# PWC.net
KiCad netlist of a schematic drawn in EAGLE
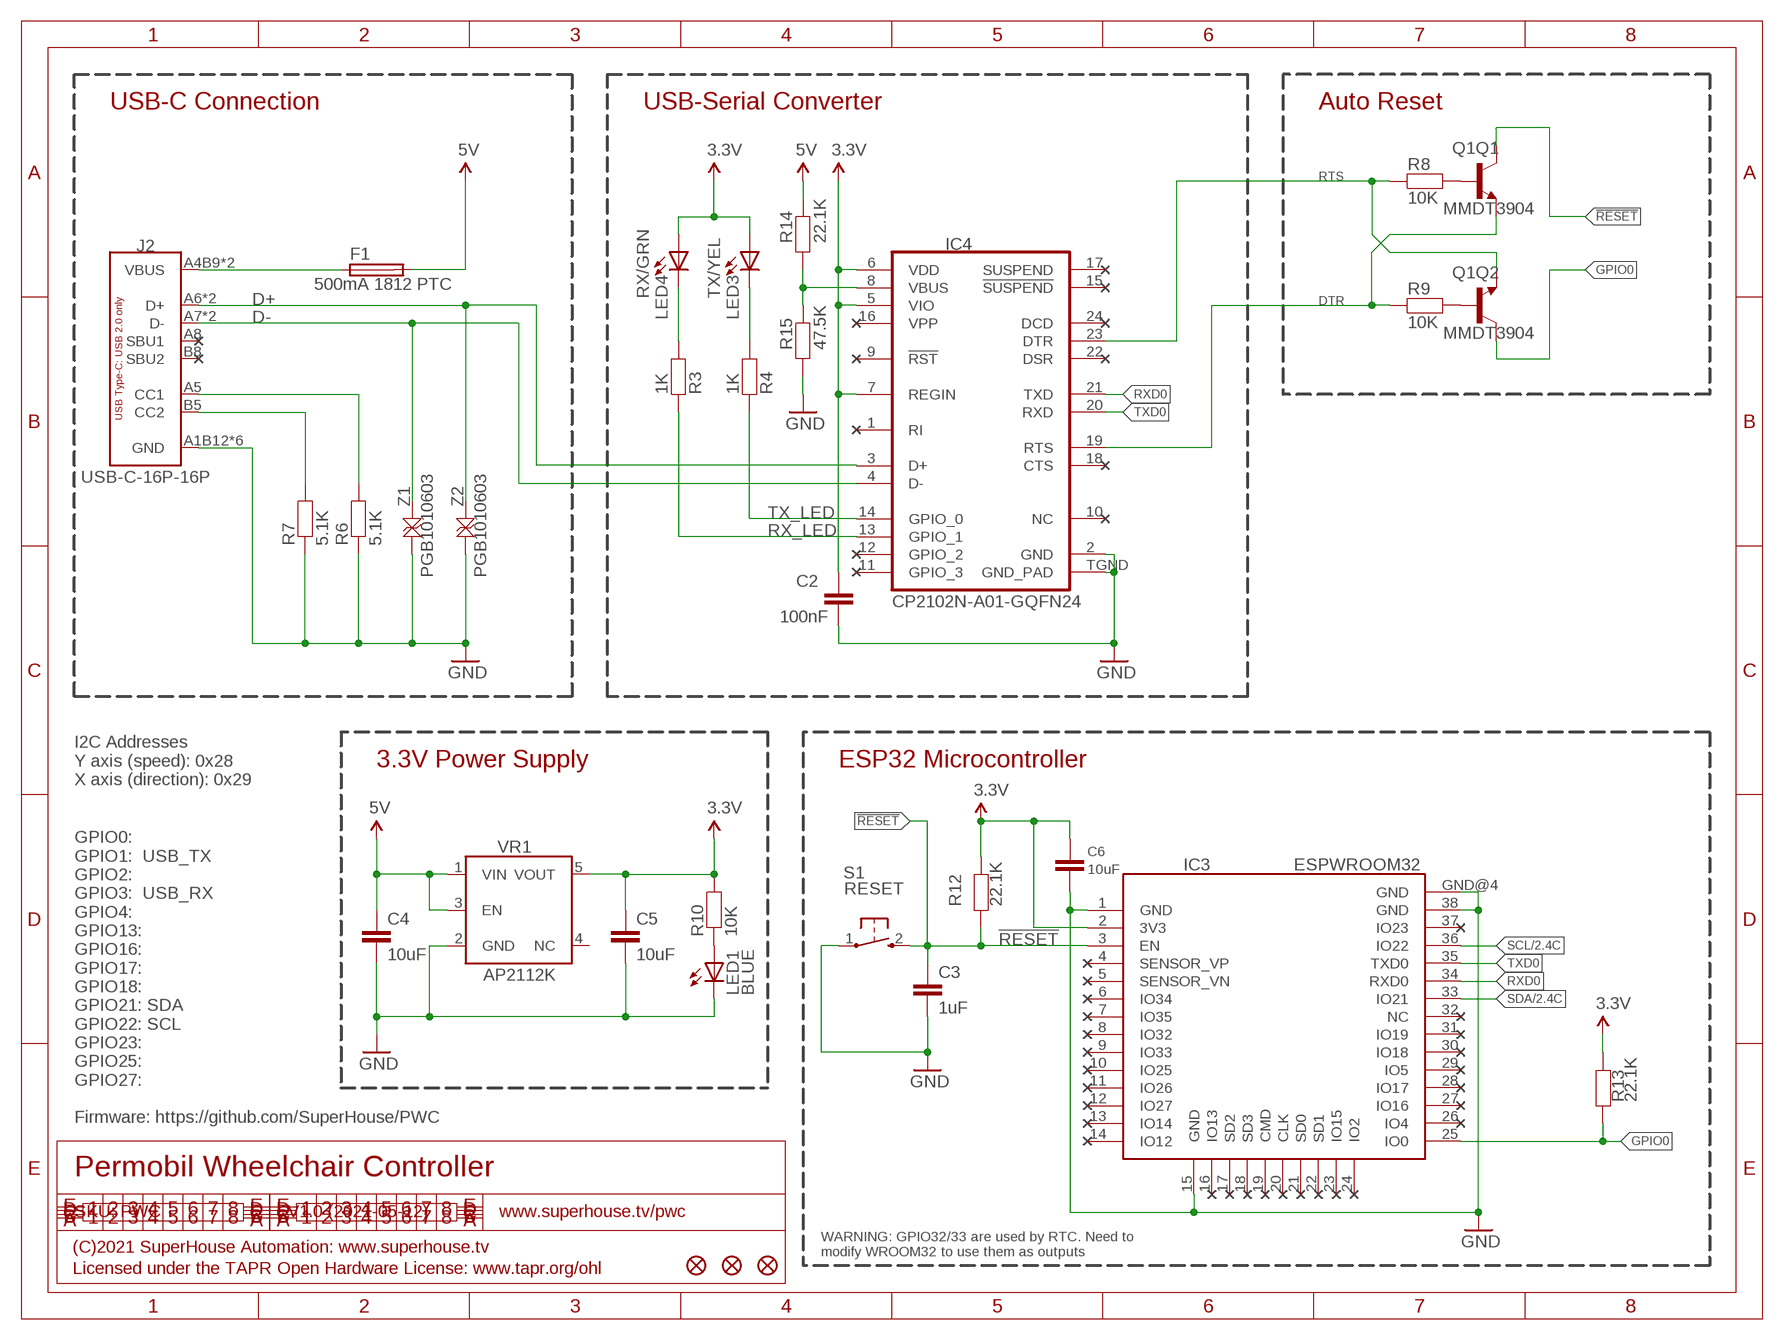
[diagram p0: schematic, sheet 1]
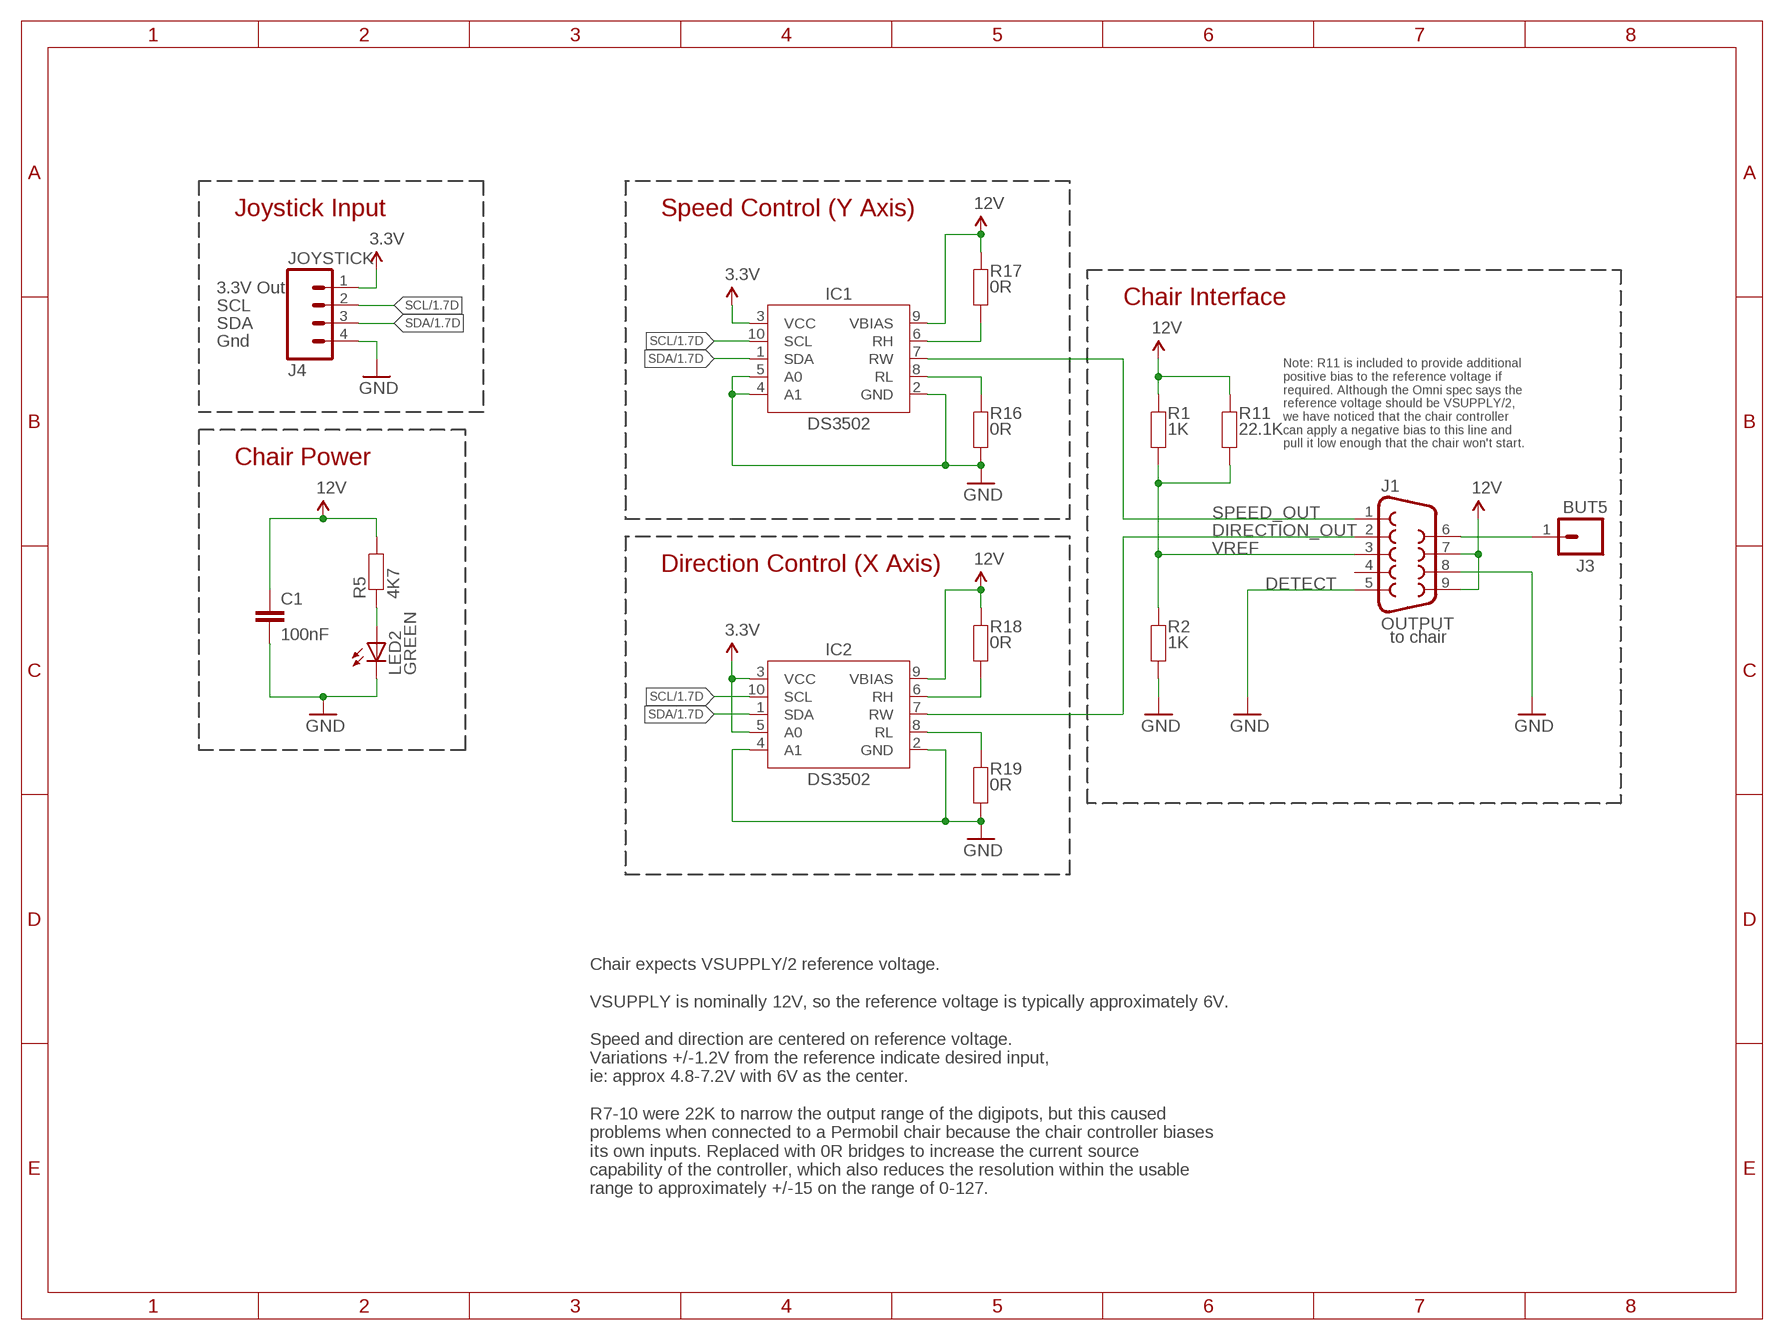
[diagram p1: schematic, sheet 2]

(export (version "E")
  (design (tool "Eeschema 10.0.6"))
  (components
    (comp (ref "C2")
      (value "100nF")
      (footprint "eagle-import:C0603")
      (libsource (lib "eagle-import") (part "CAP0603"))
    )
    (comp (ref "C3")
      (value "1uF")
      (footprint "eagle-import:C0603")
      (libsource (lib "eagle-import") (part "CAP0603"))
    )
    (comp (ref "C4")
      (value "10uF")
      (footprint "eagle-import:C0805")
      (libsource (lib "eagle-import") (part "CAP0805"))
    )
    (comp (ref "C5")
      (value "10uF")
      (footprint "eagle-import:C0805")
      (libsource (lib "eagle-import") (part "CAP0805"))
    )
    (comp (ref "C6")
      (value "10uF")
      (footprint "eagle-import:C0805")
      (libsource (lib "eagle-import") (part "CAP0805"))
    )
    (comp (ref "F1")
      (value "500mA 1812 PTC")
      (footprint "eagle-import:1812")
      (libsource (lib "eagle-import") (part "PTC-1812050"))
    )
    (comp (ref "IC3")
      (value "ESPWROOM32")
      (footprint "eagle-import:ESPWROOM32")
      (libsource (lib "eagle-import") (part "ESPWROOM32"))
    )
    (comp (ref "IC4")
      (value "CP2102N-A01-GQFN24")
      (footprint "eagle-import:QFN-24")
      (libsource (lib "eagle-import") (part "CP2104"))
    )
    (comp (ref "J2")
      (value "USB-C-16P-16P")
      (footprint "eagle-import:USB-C-16P")
      (libsource (lib "eagle-import") (part "USB-C-16P-16P"))
    )
    (comp (ref "LED1")
      (value "BLUE")
      (footprint "eagle-import:LED-0603")
      (libsource (lib "eagle-import") (part "LED0603"))
    )
    (comp (ref "LED3")
      (value "TX/YEL")
      (footprint "eagle-import:LED-0603")
      (libsource (lib "eagle-import") (part "LED0603"))
    )
    (comp (ref "LED4")
      (value "RX/GRN")
      (footprint "eagle-import:LED-0603")
      (libsource (lib "eagle-import") (part "LED0603"))
    )
    (comp (ref "Q1")
      (value "MMDT3904")
      (footprint "eagle-import:SOT-363")
      (libsource (lib "eagle-import") (part "TRANS_NPN_DUAL-MMDT3904"))
    )
    (comp (ref "R3")
      (value "1K")
      (footprint "eagle-import:R0603")
      (libsource (lib "eagle-import") (part "RESISTOR0603"))
    )
    (comp (ref "R4")
      (value "1K")
      (footprint "eagle-import:R0603")
      (libsource (lib "eagle-import") (part "RESISTOR0603"))
    )
    (comp (ref "R6")
      (value "5.1K")
      (footprint "eagle-import:R0603")
      (libsource (lib "eagle-import") (part "RESISTOR0603"))
    )
    (comp (ref "R7")
      (value "5.1K")
      (footprint "eagle-import:R0603")
      (libsource (lib "eagle-import") (part "RESISTOR0603"))
    )
    (comp (ref "R8")
      (value "10K")
      (footprint "eagle-import:R0603")
      (libsource (lib "eagle-import") (part "RESISTOR0603"))
    )
    (comp (ref "R9")
      (value "10K")
      (footprint "eagle-import:R0603")
      (libsource (lib "eagle-import") (part "RESISTOR0603"))
    )
    (comp (ref "R10")
      (value "10K")
      (footprint "eagle-import:R0603")
      (libsource (lib "eagle-import") (part "RESISTOR0603"))
    )
    (comp (ref "R12")
      (value "22.1K")
      (footprint "eagle-import:R0603")
      (libsource (lib "eagle-import") (part "RESISTOR0603"))
    )
    (comp (ref "R13")
      (value "22.1K")
      (footprint "eagle-import:R0603")
      (libsource (lib "eagle-import") (part "RESISTOR0603"))
    )
    (comp (ref "R14")
      (value "22.1K")
      (footprint "eagle-import:R0603")
      (libsource (lib "eagle-import") (part "RESISTOR0603"))
    )
    (comp (ref "R15")
      (value "47.5K")
      (footprint "eagle-import:R0603")
      (libsource (lib "eagle-import") (part "RESISTOR0603"))
    )
    (comp (ref "S1")
      (value "RESET")
      (footprint "eagle-import:TACTILE_SMT_3X4X2")
      (libsource (lib "eagle-import") (part "TAC_SWITCH_2PINSMT"))
    )
    (comp (ref "U$35")
      (value "FIDUCIAL1X2")
      (footprint "eagle-import:FIDUCIAL-1X2")
      (libsource (lib "eagle-import") (part "FIDUCIAL1X2"))
    )
    (comp (ref "U$36")
      (value "FIDUCIAL1X2")
      (footprint "eagle-import:FIDUCIAL-1X2")
      (libsource (lib "eagle-import") (part "FIDUCIAL1X2"))
    )
    (comp (ref "U$37")
      (value "FIDUCIAL1X2")
      (footprint "eagle-import:FIDUCIAL-1X2")
      (libsource (lib "eagle-import") (part "FIDUCIAL1X2"))
    )
    (comp (ref "VR1")
      (value "AP2112KSOT25")
      (footprint "eagle-import:SOT23-5")
      (libsource (lib "eagle-import") (part "AP2112KSOT25"))
    )
    (comp (ref "Z1")
      (value "PGB1010603")
      (footprint "eagle-import:TVS0603")
      (libsource (lib "eagle-import") (part "TVS0603"))
    )
    (comp (ref "Z2")
      (value "PGB1010603")
      (footprint "eagle-import:TVS0603")
      (libsource (lib "eagle-import") (part "TVS0603"))
    )
    (comp (ref "C1")
      (value "100nF")
      (footprint "eagle-import:C0603")
      (libsource (lib "eagle-import") (part "CAP0603"))
    )
    (comp (ref "IC1")
      (value "DS3502")
      (footprint "eagle-import:MSOP10")
      (libsource (lib "eagle-import") (part "DS3502"))
    )
    (comp (ref "IC2")
      (value "DS3502")
      (footprint "eagle-import:MSOP10")
      (libsource (lib "eagle-import") (part "DS3502"))
    )
    (comp (ref "J1")
      (value "OUTPUT")
      (footprint "eagle-import:DB9-PCB-SOCKET")
      (libsource (lib "eagle-import") (part "DB9-PCB-SOCKET"))
    )
    (comp (ref "J3")
      (value "BUT5")
      (footprint "eagle-import:1X01")
      (libsource (lib "eagle-import") (part "M01-PLAIN"))
    )
    (comp (ref "J4")
      (value "JOYSTICK")
      (footprint "eagle-import:1X04")
      (libsource (lib "eagle-import") (part "M04-PLAIN"))
    )
    (comp (ref "LED2")
      (value "GREEN")
      (footprint "eagle-import:LED-0603")
      (libsource (lib "eagle-import") (part "LED0603"))
    )
    (comp (ref "R1")
      (value "1K")
      (footprint "eagle-import:R0603")
      (libsource (lib "eagle-import") (part "RESISTOR0603"))
    )
    (comp (ref "R2")
      (value "1K")
      (footprint "eagle-import:R0603")
      (libsource (lib "eagle-import") (part "RESISTOR0603"))
    )
    (comp (ref "R5")
      (value "4K7")
      (footprint "eagle-import:R0603")
      (libsource (lib "eagle-import") (part "RESISTOR0603"))
    )
    (comp (ref "R11")
      (value "22.1K")
      (footprint "eagle-import:R0603")
      (libsource (lib "eagle-import") (part "RESISTOR0603"))
    )
    (comp (ref "R16")
      (value "0R")
      (footprint "eagle-import:R0603")
      (libsource (lib "eagle-import") (part "RESISTOR0603"))
    )
    (comp (ref "R17")
      (value "0R")
      (footprint "eagle-import:R0603")
      (libsource (lib "eagle-import") (part "RESISTOR0603"))
    )
    (comp (ref "R18")
      (value "0R")
      (footprint "eagle-import:R0603")
      (libsource (lib "eagle-import") (part "RESISTOR0603"))
    )
    (comp (ref "R19")
      (value "0R")
      (footprint "eagle-import:R0603")
      (libsource (lib "eagle-import") (part "RESISTOR0603"))
    )
  )
  (nets
    (net (code "1") (name "3.3V") (class "Default")
      (node (ref "C2") (pin "1") (pinfunction "1_1") (pintype "passive"))
      (node (ref "C5") (pin "1") (pinfunction "1_1") (pintype "passive"))
      (node (ref "C6") (pin "1") (pinfunction "1_1") (pintype "passive"))
      (node (ref "IC1") (pin "3") (pinfunction "VCC_3") (pintype "power_in"))
      (node (ref "IC2") (pin "3") (pinfunction "VCC_3") (pintype "power_in"))
      (node (ref "IC2") (pin "5") (pinfunction "A0_5") (pintype "input"))
      (node (ref "IC3") (pin "2") (pinfunction "3V3_2") (pintype "power_in"))
      (node (ref "IC4") (pin "5") (pinfunction "VIO_5") (pintype "bidirectional"))
      (node (ref "IC4") (pin "6") (pinfunction "VDD_6") (pintype "power_in"))
      (node (ref "IC4") (pin "7") (pinfunction "REGIN_7") (pintype "power_in"))
      (node (ref "J4") (pin "1") (pinfunction "1_1") (pintype "passive"))
      (node (ref "LED3") (pin "A") (pinfunction "A_A") (pintype "passive"))
      (node (ref "LED4") (pin "A") (pinfunction "A_A") (pintype "passive"))
      (node (ref "R10") (pin "2") (pinfunction "2_2") (pintype "passive"))
      (node (ref "R12") (pin "1") (pinfunction "1_1") (pintype "passive"))
      (node (ref "R13") (pin "1") (pinfunction "1_1") (pintype "passive"))
      (node (ref "VR1") (pin "5") (pinfunction "VOUT_5") (pintype "bidirectional"))
    )
    (net (code "2") (name "5V") (class "Default")
      (node (ref "C4") (pin "1") (pinfunction "1_1") (pintype "passive"))
      (node (ref "F1") (pin "2") (pinfunction "2_2") (pintype "passive"))
      (node (ref "R14") (pin "2") (pinfunction "2_2") (pintype "passive"))
      (node (ref "VR1") (pin "1") (pinfunction "VIN_1") (pintype "bidirectional"))
      (node (ref "VR1") (pin "3") (pinfunction "EN_3") (pintype "bidirectional"))
    )
    (net (code "3") (name "12V") (class "Default")
      (node (ref "C1") (pin "1") (pinfunction "1_1") (pintype "passive"))
      (node (ref "IC1") (pin "9") (pinfunction "VBIAS_9") (pintype "power_in"))
      (node (ref "IC2") (pin "9") (pinfunction "VBIAS_9") (pintype "power_in"))
      (node (ref "J1") (pin "7") (pinfunction "7_7") (pintype "passive"))
      (node (ref "J1") (pin "9") (pinfunction "9_9") (pintype "passive"))
      (node (ref "R1") (pin "2") (pinfunction "2_2") (pintype "passive"))
      (node (ref "R11") (pin "2") (pinfunction "2_2") (pintype "passive"))
      (node (ref "R17") (pin "2") (pinfunction "2_2") (pintype "passive"))
      (node (ref "R18") (pin "2") (pinfunction "2_2") (pintype "passive"))
      (node (ref "R5") (pin "2") (pinfunction "2_2") (pintype "passive"))
    )
    (net (code "4") (name "D+") (class "Default")
      (node (ref "IC4") (pin "3") (pinfunction "D+_3") (pintype "bidirectional"))
      (node (ref "J2") (pin "A6") (pinfunction "D+_A6") (pintype "bidirectional"))
      (node (ref "J2") (pin "B6") (pinfunction "D+_B6") (pintype "bidirectional"))
      (node (ref "Z2") (pin "2") (pinfunction "2_2") (pintype "passive"))
    )
    (net (code "5") (name "D-") (class "Default")
      (node (ref "IC4") (pin "4") (pinfunction "D-_4") (pintype "bidirectional"))
      (node (ref "J2") (pin "A7") (pinfunction "D-_A7") (pintype "bidirectional"))
      (node (ref "J2") (pin "B7") (pinfunction "D-_B7") (pintype "bidirectional"))
      (node (ref "Z1") (pin "2") (pinfunction "2_2") (pintype "passive"))
    )
    (net (code "6") (name "DIRECTION_OUT") (class "Default")
      (node (ref "IC2") (pin "7") (pinfunction "RW_7") (pintype "passive"))
      (node (ref "J1") (pin "2") (pinfunction "2_2") (pintype "passive"))
    )
    (net (code "7") (name "DTR") (class "Default")
      (node (ref "IC4") (pin "23") (pinfunction "DTR_23") (pintype "output"))
      (node (ref "Q1") (pin "1") (pinfunction "E_1") (pintype "passive"))
      (node (ref "R8") (pin "1") (pinfunction "1_1") (pintype "passive"))
    )
    (net (code "8") (name "GND") (class "Default")
      (node (ref "C1") (pin "2") (pinfunction "2_2") (pintype "passive"))
      (node (ref "C2") (pin "2") (pinfunction "2_2") (pintype "passive"))
      (node (ref "C3") (pin "2") (pinfunction "2_2") (pintype "passive"))
      (node (ref "C4") (pin "2") (pinfunction "2_2") (pintype "passive"))
      (node (ref "C5") (pin "2") (pinfunction "2_2") (pintype "passive"))
      (node (ref "C6") (pin "2") (pinfunction "2_2") (pintype "passive"))
      (node (ref "IC1") (pin "2") (pinfunction "GND_2") (pintype "power_in"))
      (node (ref "IC1") (pin "4") (pinfunction "A1_4") (pintype "input"))
      (node (ref "IC1") (pin "5") (pinfunction "A0_5") (pintype "input"))
      (node (ref "IC2") (pin "2") (pinfunction "GND_2") (pintype "power_in"))
      (node (ref "IC2") (pin "4") (pinfunction "A1_4") (pintype "input"))
      (node (ref "IC3") (pin "1") (pinfunction "GND_1") (pintype "power_in"))
      (node (ref "IC3") (pin "15") (pinfunction "GND_15") (pintype "power_in"))
      (node (ref "IC3") (pin "38") (pinfunction "GND_38") (pintype "power_in"))
      (node (ref "IC3") (pin "GND@4") (pinfunction "GND_GND@4") (pintype "power_in"))
      (node (ref "IC4") (pin "2") (pinfunction "GND_2") (pintype "power_in"))
      (node (ref "IC4") (pin "TGND") (pinfunction "GND_PAD_TGND") (pintype "power_in"))
      (node (ref "J1") (pin "5") (pinfunction "5_5") (pintype "passive"))
      (node (ref "J1") (pin "8") (pinfunction "8_8") (pintype "passive"))
      (node (ref "J2") (pin "A12B1") (pinfunction "GND_A12B1") (pintype "power_in"))
      (node (ref "J2") (pin "A1B12") (pinfunction "GND_A1B12") (pintype "power_in"))
      (node (ref "J2") (pin "FIX1") (pinfunction "GND_FIX1") (pintype "power_in"))
      (node (ref "J2") (pin "FIX2") (pinfunction "GND_FIX2") (pintype "power_in"))
      (node (ref "J2") (pin "FIX3") (pinfunction "GND_FIX3") (pintype "power_in"))
      (node (ref "J2") (pin "FIX4") (pinfunction "GND_FIX4") (pintype "power_in"))
      (node (ref "J4") (pin "4") (pinfunction "4_4") (pintype "passive"))
      (node (ref "LED1") (pin "C") (pinfunction "C_C") (pintype "passive"))
      (node (ref "LED2") (pin "C") (pinfunction "C_C") (pintype "passive"))
      (node (ref "R15") (pin "1") (pinfunction "1_1") (pintype "passive"))
      (node (ref "R16") (pin "1") (pinfunction "1_1") (pintype "passive"))
      (node (ref "R19") (pin "1") (pinfunction "1_1") (pintype "passive"))
      (node (ref "R2") (pin "1") (pinfunction "1_1") (pintype "passive"))
      (node (ref "R6") (pin "1") (pinfunction "1_1") (pintype "passive"))
      (node (ref "R7") (pin "1") (pinfunction "1_1") (pintype "passive"))
      (node (ref "S1") (pin "1") (pinfunction "P_1") (pintype "passive"))
      (node (ref "VR1") (pin "2") (pinfunction "GND_2") (pintype "bidirectional"))
      (node (ref "Z1") (pin "1") (pinfunction "1_1") (pintype "passive"))
      (node (ref "Z2") (pin "1") (pinfunction "1_1") (pintype "passive"))
    )
    (net (code "9") (name "GPIO0") (class "Default")
      (node (ref "IC3") (pin "25") (pinfunction "IO0_25") (pintype "bidirectional"))
      (node (ref "Q1") (pin "6") (pinfunction "C_6") (pintype "passive"))
      (node (ref "R13") (pin "2") (pinfunction "2_2") (pintype "passive"))
    )
    (net (code "10") (name "Net-(F1-Pad1)") (class "Default")
      (node (ref "F1") (pin "1") (pinfunction "1_1") (pintype "passive"))
      (node (ref "J2") (pin "A4B9") (pinfunction "VBUS_A4B9") (pintype "power_in"))
      (node (ref "J2") (pin "A9B4") (pinfunction "VBUS_A9B4") (pintype "power_in"))
    )
    (net (code "11") (name "Net-(IC1-RH)") (class "Default")
      (node (ref "IC1") (pin "6") (pinfunction "RH_6") (pintype "passive"))
      (node (ref "R17") (pin "1") (pinfunction "1_1") (pintype "passive"))
    )
    (net (code "12") (name "Net-(IC1-RL)") (class "Default")
      (node (ref "IC1") (pin "8") (pinfunction "RL_8") (pintype "passive"))
      (node (ref "R16") (pin "2") (pinfunction "2_2") (pintype "passive"))
    )
    (net (code "13") (name "Net-(IC2-RH)") (class "Default")
      (node (ref "IC2") (pin "6") (pinfunction "RH_6") (pintype "passive"))
      (node (ref "R18") (pin "1") (pinfunction "1_1") (pintype "passive"))
    )
    (net (code "14") (name "Net-(IC2-RL)") (class "Default")
      (node (ref "IC2") (pin "8") (pinfunction "RL_8") (pintype "passive"))
      (node (ref "R19") (pin "2") (pinfunction "2_2") (pintype "passive"))
    )
    (net (code "15") (name "Net-(IC4-VBUS)") (class "Default")
      (node (ref "IC4") (pin "8") (pinfunction "VBUS_8") (pintype "bidirectional"))
      (node (ref "R14") (pin "1") (pinfunction "1_1") (pintype "passive"))
      (node (ref "R15") (pin "2") (pinfunction "2_2") (pintype "passive"))
    )
    (net (code "16") (name "Net-(J1-Pad6)") (class "Default")
      (node (ref "J1") (pin "6") (pinfunction "6_6") (pintype "passive"))
      (node (ref "J3") (pin "1") (pinfunction "1_1") (pintype "passive"))
    )
    (net (code "17") (name "Net-(J2-CC1)") (class "Default")
      (node (ref "J2") (pin "A5") (pinfunction "CC1_A5") (pintype "bidirectional"))
      (node (ref "R6") (pin "2") (pinfunction "2_2") (pintype "passive"))
    )
    (net (code "18") (name "Net-(J2-CC2)") (class "Default")
      (node (ref "J2") (pin "B5") (pinfunction "CC2_B5") (pintype "bidirectional"))
      (node (ref "R7") (pin "2") (pinfunction "2_2") (pintype "passive"))
    )
    (net (code "19") (name "Net-(LED1-PadA)") (class "Default")
      (node (ref "LED1") (pin "A") (pinfunction "A_A") (pintype "passive"))
      (node (ref "R10") (pin "1") (pinfunction "1_1") (pintype "passive"))
    )
    (net (code "20") (name "Net-(LED2-PadA)") (class "Default")
      (node (ref "LED2") (pin "A") (pinfunction "A_A") (pintype "passive"))
      (node (ref "R5") (pin "1") (pinfunction "1_1") (pintype "passive"))
    )
    (net (code "21") (name "Net-(LED3-PadC)") (class "Default")
      (node (ref "LED3") (pin "C") (pinfunction "C_C") (pintype "passive"))
      (node (ref "R4") (pin "2") (pinfunction "2_2") (pintype "passive"))
    )
    (net (code "22") (name "Net-(LED4-PadC)") (class "Default")
      (node (ref "LED4") (pin "C") (pinfunction "C_C") (pintype "passive"))
      (node (ref "R3") (pin "2") (pinfunction "2_2") (pintype "passive"))
    )
    (net (code "23") (name "Net-(Q1A-B)") (class "Default")
      (node (ref "Q1") (pin "5") (pinfunction "B_5") (pintype "passive"))
      (node (ref "R8") (pin "2") (pinfunction "2_2") (pintype "passive"))
    )
    (net (code "24") (name "Net-(Q1B-B)") (class "Default")
      (node (ref "Q1") (pin "2") (pinfunction "B_2") (pintype "passive"))
      (node (ref "R9") (pin "2") (pinfunction "2_2") (pintype "passive"))
    )
    (net (code "25") (name "RTS") (class "Default")
      (node (ref "IC4") (pin "19") (pinfunction "RTS_19") (pintype "output"))
      (node (ref "Q1") (pin "4") (pinfunction "E_4") (pintype "passive"))
      (node (ref "R9") (pin "1") (pinfunction "1_1") (pintype "passive"))
    )
    (net (code "26") (name "RXD0") (class "Default")
      (node (ref "IC3") (pin "34") (pinfunction "RXD0_34") (pintype "bidirectional"))
      (node (ref "IC4") (pin "21") (pinfunction "TXD_21") (pintype "output"))
    )
    (net (code "27") (name "RX_LED") (class "Default")
      (node (ref "IC4") (pin "13") (pinfunction "GPIO_1_13") (pintype "bidirectional"))
      (node (ref "R3") (pin "1") (pinfunction "1_1") (pintype "passive"))
    )
    (net (code "28") (name "SCL") (class "Default")
      (node (ref "IC1") (pin "10") (pinfunction "SCL_10") (pintype "input"))
      (node (ref "IC2") (pin "10") (pinfunction "SCL_10") (pintype "input"))
      (node (ref "IC3") (pin "36") (pinfunction "IO22_36") (pintype "bidirectional"))
      (node (ref "J4") (pin "2") (pinfunction "2_2") (pintype "passive"))
    )
    (net (code "29") (name "SDA") (class "Default")
      (node (ref "IC1") (pin "1") (pinfunction "SDA_1") (pintype "bidirectional"))
      (node (ref "IC2") (pin "1") (pinfunction "SDA_1") (pintype "bidirectional"))
      (node (ref "IC3") (pin "33") (pinfunction "IO21_33") (pintype "bidirectional"))
      (node (ref "J4") (pin "3") (pinfunction "3_3") (pintype "passive"))
    )
    (net (code "30") (name "SPEED_OUT") (class "Default")
      (node (ref "IC1") (pin "7") (pinfunction "RW_7") (pintype "passive"))
      (node (ref "J1") (pin "1") (pinfunction "1_1") (pintype "passive"))
    )
    (net (code "31") (name "TXD0") (class "Default")
      (node (ref "IC3") (pin "35") (pinfunction "TXD0_35") (pintype "bidirectional"))
      (node (ref "IC4") (pin "20") (pinfunction "RXD_20") (pintype "input"))
    )
    (net (code "32") (name "TX_LED") (class "Default")
      (node (ref "IC4") (pin "14") (pinfunction "GPIO_0_14") (pintype "bidirectional"))
      (node (ref "R4") (pin "1") (pinfunction "1_1") (pintype "passive"))
    )
    (net (code "33") (name "VREF") (class "Default")
      (node (ref "J1") (pin "3") (pinfunction "3_3") (pintype "passive"))
      (node (ref "R1") (pin "1") (pinfunction "1_1") (pintype "passive"))
      (node (ref "R11") (pin "1") (pinfunction "1_1") (pintype "passive"))
      (node (ref "R2") (pin "2") (pinfunction "2_2") (pintype "passive"))
    )
    (net (code "34") (name "unconnected-(IC3-CLK-Pad20)") (class "Default")
      (node (ref "IC3") (pin "20") (pinfunction "CLK_20") (pintype "bidirectional"))
    )
    (net (code "35") (name "unconnected-(IC3-CMD-Pad19)") (class "Default")
      (node (ref "IC3") (pin "19") (pinfunction "CMD_19") (pintype "bidirectional"))
    )
    (net (code "36") (name "unconnected-(IC3-IO2-Pad24)") (class "Default")
      (node (ref "IC3") (pin "24") (pinfunction "IO2_24") (pintype "bidirectional"))
    )
    (net (code "37") (name "unconnected-(IC3-IO4-Pad26)") (class "Default")
      (node (ref "IC3") (pin "26") (pinfunction "IO4_26") (pintype "bidirectional"))
    )
    (net (code "38") (name "unconnected-(IC3-IO5-Pad29)") (class "Default")
      (node (ref "IC3") (pin "29") (pinfunction "IO5_29") (pintype "bidirectional"))
    )
    (net (code "39") (name "unconnected-(IC3-IO12-Pad14)") (class "Default")
      (node (ref "IC3") (pin "14") (pinfunction "IO12_14") (pintype "bidirectional"))
    )
    (net (code "40") (name "unconnected-(IC3-IO13-Pad16)") (class "Default")
      (node (ref "IC3") (pin "16") (pinfunction "IO13_16") (pintype "bidirectional"))
    )
    (net (code "41") (name "unconnected-(IC3-IO14-Pad13)") (class "Default")
      (node (ref "IC3") (pin "13") (pinfunction "IO14_13") (pintype "bidirectional"))
    )
    (net (code "42") (name "unconnected-(IC3-IO15-Pad23)") (class "Default")
      (node (ref "IC3") (pin "23") (pinfunction "IO15_23") (pintype "bidirectional"))
    )
    (net (code "43") (name "unconnected-(IC3-IO16-Pad27)") (class "Default")
      (node (ref "IC3") (pin "27") (pinfunction "IO16_27") (pintype "bidirectional"))
    )
    (net (code "44") (name "unconnected-(IC3-IO17-Pad28)") (class "Default")
      (node (ref "IC3") (pin "28") (pinfunction "IO17_28") (pintype "bidirectional"))
    )
    (net (code "45") (name "unconnected-(IC3-IO18-Pad30)") (class "Default")
      (node (ref "IC3") (pin "30") (pinfunction "IO18_30") (pintype "bidirectional"))
    )
    (net (code "46") (name "unconnected-(IC3-IO19-Pad31)") (class "Default")
      (node (ref "IC3") (pin "31") (pinfunction "IO19_31") (pintype "bidirectional"))
    )
    (net (code "47") (name "unconnected-(IC3-IO23-Pad37)") (class "Default")
      (node (ref "IC3") (pin "37") (pinfunction "IO23_37") (pintype "bidirectional"))
    )
    (net (code "48") (name "unconnected-(IC3-IO25-Pad10)") (class "Default")
      (node (ref "IC3") (pin "10") (pinfunction "IO25_10") (pintype "bidirectional"))
    )
    (net (code "49") (name "unconnected-(IC3-IO26-Pad11)") (class "Default")
      (node (ref "IC3") (pin "11") (pinfunction "IO26_11") (pintype "bidirectional"))
    )
    (net (code "50") (name "unconnected-(IC3-IO27-Pad12)") (class "Default")
      (node (ref "IC3") (pin "12") (pinfunction "IO27_12") (pintype "bidirectional"))
    )
    (net (code "51") (name "unconnected-(IC3-IO32-Pad8)") (class "Default")
      (node (ref "IC3") (pin "8") (pinfunction "IO32_8") (pintype "bidirectional"))
    )
    (net (code "52") (name "unconnected-(IC3-IO33-Pad9)") (class "Default")
      (node (ref "IC3") (pin "9") (pinfunction "IO33_9") (pintype "bidirectional"))
    )
    (net (code "53") (name "unconnected-(IC3-IO34-Pad6)") (class "Default")
      (node (ref "IC3") (pin "6") (pinfunction "IO34_6") (pintype "bidirectional"))
    )
    (net (code "54") (name "unconnected-(IC3-IO35-Pad7)") (class "Default")
      (node (ref "IC3") (pin "7") (pinfunction "IO35_7") (pintype "bidirectional"))
    )
    (net (code "55") (name "unconnected-(IC3-NC-Pad32)") (class "Default")
      (node (ref "IC3") (pin "32") (pinfunction "NC_32") (pintype "bidirectional"))
    )
    (net (code "56") (name "unconnected-(IC3-SD0-Pad21)") (class "Default")
      (node (ref "IC3") (pin "21") (pinfunction "SD0_21") (pintype "bidirectional"))
    )
    (net (code "57") (name "unconnected-(IC3-SD1-Pad22)") (class "Default")
      (node (ref "IC3") (pin "22") (pinfunction "SD1_22") (pintype "bidirectional"))
    )
    (net (code "58") (name "unconnected-(IC3-SD2-Pad17)") (class "Default")
      (node (ref "IC3") (pin "17") (pinfunction "SD2_17") (pintype "bidirectional"))
    )
    (net (code "59") (name "unconnected-(IC3-SD3-Pad18)") (class "Default")
      (node (ref "IC3") (pin "18") (pinfunction "SD3_18") (pintype "bidirectional"))
    )
    (net (code "60") (name "unconnected-(IC3-SENSOR_VN-Pad5)") (class "Default")
      (node (ref "IC3") (pin "5") (pinfunction "SENSOR_VN_5") (pintype "bidirectional"))
    )
    (net (code "61") (name "unconnected-(IC3-SENSOR_VP-Pad4)") (class "Default")
      (node (ref "IC3") (pin "4") (pinfunction "SENSOR_VP_4") (pintype "bidirectional"))
    )
    (net (code "62") (name "unconnected-(IC4-CTS-Pad18)") (class "Default")
      (node (ref "IC4") (pin "18") (pinfunction "CTS_18") (pintype "input"))
    )
    (net (code "63") (name "unconnected-(IC4-DCD-Pad24)") (class "Default")
      (node (ref "IC4") (pin "24") (pinfunction "DCD_24") (pintype "input"))
    )
    (net (code "64") (name "unconnected-(IC4-DSR-Pad22)") (class "Default")
      (node (ref "IC4") (pin "22") (pinfunction "DSR_22") (pintype "input"))
    )
    (net (code "65") (name "unconnected-(IC4-GPIO_2-Pad12)") (class "Default")
      (node (ref "IC4") (pin "12") (pinfunction "GPIO_2_12") (pintype "bidirectional"))
    )
    (net (code "66") (name "unconnected-(IC4-GPIO_3-Pad11)") (class "Default")
      (node (ref "IC4") (pin "11") (pinfunction "GPIO_3_11") (pintype "bidirectional"))
    )
    (net (code "67") (name "unconnected-(IC4-NC-Pad10)") (class "Default")
      (node (ref "IC4") (pin "10") (pinfunction "NC_10") (pintype "input"))
    )
    (net (code "68") (name "unconnected-(IC4-RI-Pad1)") (class "Default")
      (node (ref "IC4") (pin "1") (pinfunction "RI_1") (pintype "input"))
    )
    (net (code "69") (name "unconnected-(IC4-SUSPEND-Pad17)") (class "Default")
      (node (ref "IC4") (pin "17") (pinfunction "SUSPEND_17") (pintype "output"))
    )
    (net (code "70") (name "unconnected-(IC4-VPP-Pad16)") (class "Default")
      (node (ref "IC4") (pin "16") (pinfunction "VPP_16") (pintype "bidirectional"))
    )
    (net (code "71") (name "unconnected-(IC4-~{RST}-Pad9)") (class "Default")
      (node (ref "IC4") (pin "9") (pinfunction "~{RST}_9") (pintype "bidirectional"))
    )
    (net (code "72") (name "unconnected-(IC4-~{SUSPEND}-Pad15)") (class "Default")
      (node (ref "IC4") (pin "15") (pinfunction "~{SUSPEND}_15") (pintype "output"))
    )
    (net (code "73") (name "unconnected-(J1-Pad4)") (class "Default")
      (node (ref "J1") (pin "4") (pinfunction "4_4") (pintype "passive"))
    )
    (net (code "74") (name "unconnected-(J2-SBU1-PadA8)") (class "Default")
      (node (ref "J2") (pin "A8") (pinfunction "SBU1_A8") (pintype "bidirectional"))
    )
    (net (code "75") (name "unconnected-(J2-SBU2-PadB8)") (class "Default")
      (node (ref "J2") (pin "B8") (pinfunction "SBU2_B8") (pintype "bidirectional"))
    )
    (net (code "76") (name "unconnected-(VR1-NC-Pad4)") (class "Default")
      (node (ref "VR1") (pin "4") (pinfunction "NC_4") (pintype "bidirectional"))
    )
    (net (code "77") (name "~{RESET}") (class "Default")
      (node (ref "C3") (pin "1") (pinfunction "1_1") (pintype "passive"))
      (node (ref "IC3") (pin "3") (pinfunction "EN_3") (pintype "bidirectional"))
      (node (ref "Q1") (pin "3") (pinfunction "C_3") (pintype "passive"))
      (node (ref "R12") (pin "2") (pinfunction "2_2") (pintype "passive"))
      (node (ref "S1") (pin "2") (pinfunction "S_2") (pintype "passive"))
    )
  )
)
